# UVBoxSchematic_1_0.net
KiCad netlist of a schematic drawn in EAGLE
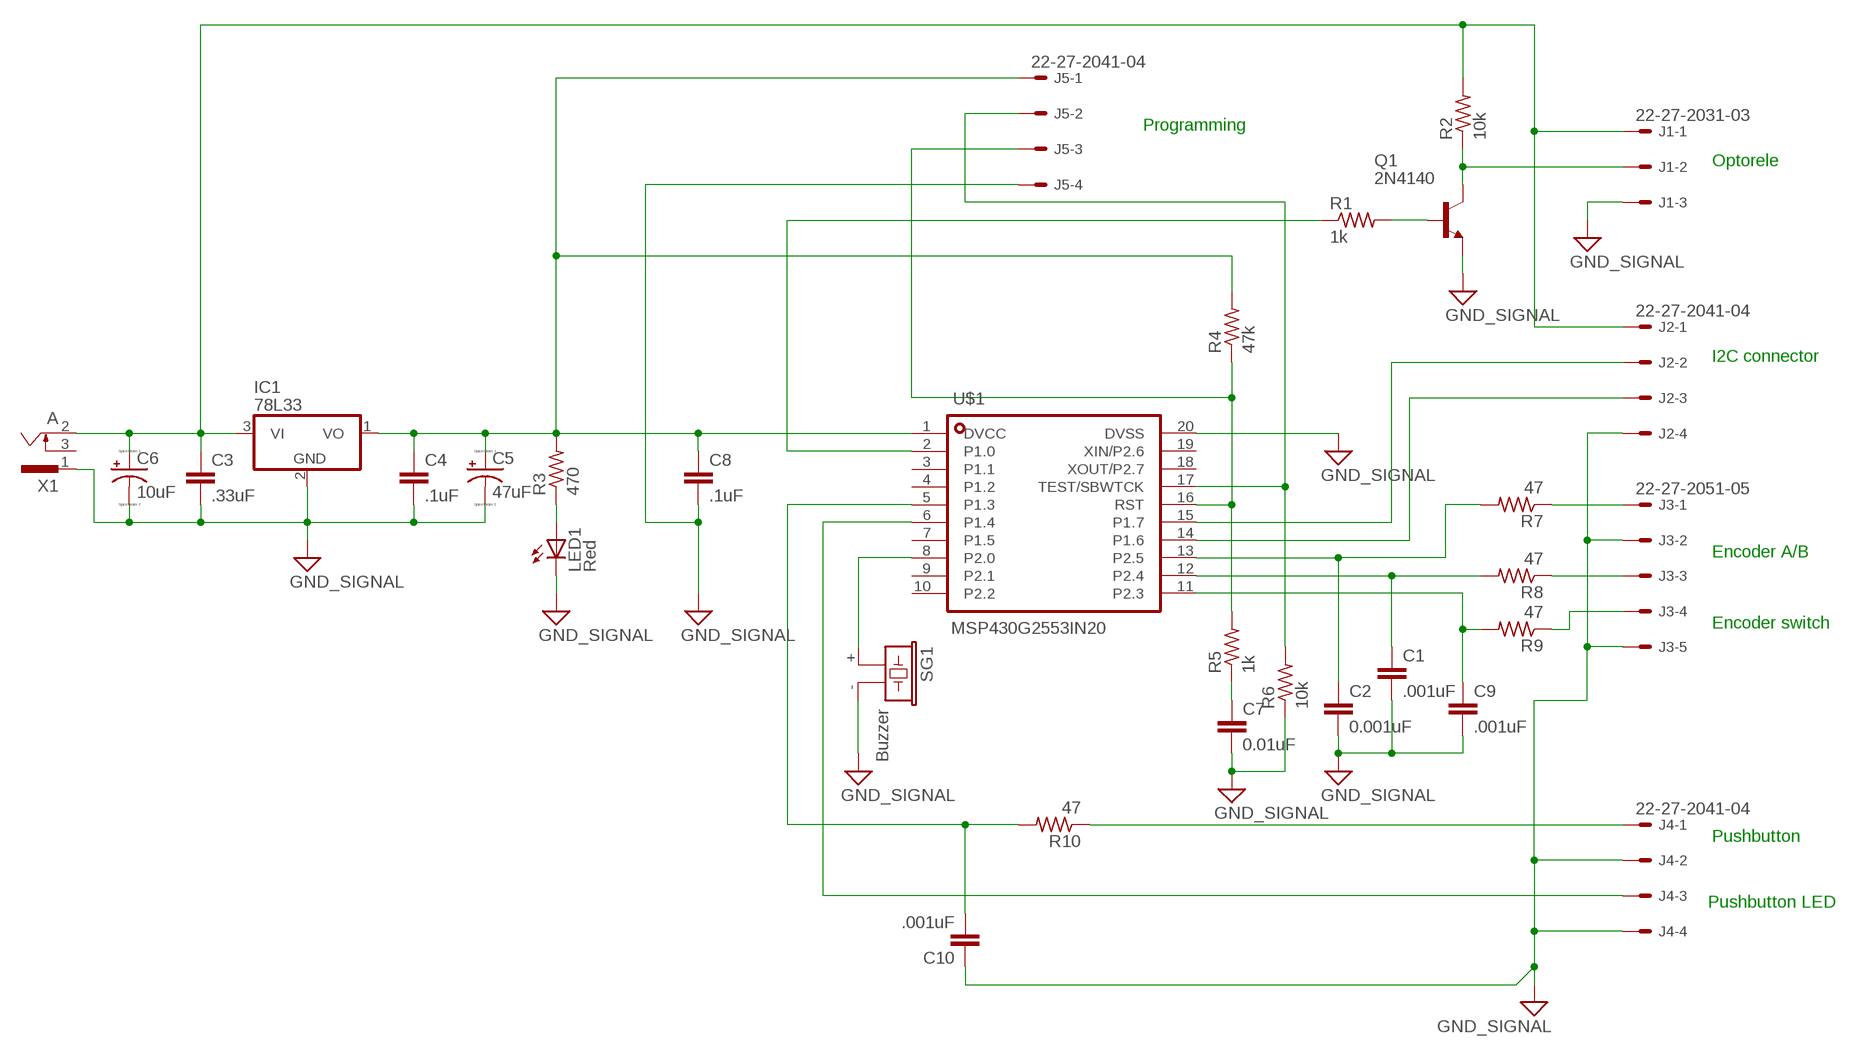
[diagram p0: schematic, sheet 1]

(export (version "E")
  (design (tool "Eeschema 10.0.6"))
  (components
    (comp (ref "C1")
      (value ".001uF")
      (footprint "eagle-import:C2.5-2")
      (libsource (lib "eagle-import") (part "C2.5/2"))
    )
    (comp (ref "C2")
      (value "0.001uF")
      (footprint "eagle-import:C2.5-2")
      (libsource (lib "eagle-import") (part "C2.5/2"))
    )
    (comp (ref "C3")
      (value ".33uF")
      (footprint "eagle-import:C2.5-2")
      (libsource (lib "eagle-import") (part "C2.5/2"))
    )
    (comp (ref "C4")
      (value ".1uF")
      (footprint "eagle-import:C2.5-2")
      (libsource (lib "eagle-import") (part "C2.5/2"))
    )
    (comp (ref "C5")
      (value "47uF")
      (footprint "eagle-import:B45181A")
      (libsource (lib "eagle-import") (part "CPOL-USB45181A"))
    )
    (comp (ref "C6")
      (value "10uF")
      (footprint "eagle-import:B45181A")
      (libsource (lib "eagle-import") (part "CPOL-USB45181A"))
    )
    (comp (ref "C7")
      (value "0.01uF")
      (footprint "eagle-import:C2.5-2")
      (libsource (lib "eagle-import") (part "C2.5/2"))
    )
    (comp (ref "C8")
      (value ".1uF")
      (footprint "eagle-import:C2.5-2")
      (libsource (lib "eagle-import") (part "C2.5/2"))
    )
    (comp (ref "C9")
      (value ".001uF")
      (footprint "eagle-import:C2.5-2")
      (libsource (lib "eagle-import") (part "C2.5/2"))
    )
    (comp (ref "C10")
      (value ".001uF")
      (footprint "eagle-import:C2.5-2")
      (libsource (lib "eagle-import") (part "C2.5/2"))
    )
    (comp (ref "IC1")
      (value "78L33")
      (footprint "eagle-import:TO92")
      (libsource (lib "eagle-import") (part "78ZL05"))
    )
    (comp (ref "J1")
      (value "22-27-2031-03")
      (footprint "eagle-import:6410-03")
      (libsource (lib "eagle-import") (part "22-?-0327-2031"))
    )
    (comp (ref "J2")
      (value "22-27-2041-04")
      (footprint "eagle-import:6410-04")
      (libsource (lib "eagle-import") (part "22-?-0427-2041"))
    )
    (comp (ref "J3")
      (value "22-27-2051-05")
      (footprint "eagle-import:6410-05")
      (libsource (lib "eagle-import") (part "22-?-0527-2051"))
    )
    (comp (ref "J4")
      (value "22-27-2041-04")
      (footprint "eagle-import:6410-04")
      (libsource (lib "eagle-import") (part "22-?-0427-2041"))
    )
    (comp (ref "J5")
      (value "22-27-2041-04")
      (footprint "eagle-import:6410-04")
      (libsource (lib "eagle-import") (part "22-?-0427-2041"))
    )
    (comp (ref "LED1")
      (value "Red")
      (footprint "eagle-import:LED3MM")
      (libsource (lib "eagle-import") (part "LED3MM"))
    )
    (comp (ref "Q1")
      (value "2N4140")
      (footprint "eagle-import:TO18")
      (libsource (lib "eagle-import") (part "2N4104"))
    )
    (comp (ref "R1")
      (value "1k")
      (footprint "eagle-import:0204_7")
      (libsource (lib "eagle-import") (part "R-US_0204/7"))
    )
    (comp (ref "R2")
      (value "10k")
      (footprint "eagle-import:0204_7")
      (libsource (lib "eagle-import") (part "R-US_0204/7"))
    )
    (comp (ref "R3")
      (value "470")
      (footprint "eagle-import:0204_7")
      (libsource (lib "eagle-import") (part "R-US_0204/7"))
    )
    (comp (ref "R4")
      (value "47k")
      (footprint "eagle-import:0204_7")
      (libsource (lib "eagle-import") (part "R-US_0204/7"))
    )
    (comp (ref "R5")
      (value "1k")
      (footprint "eagle-import:0204_7")
      (libsource (lib "eagle-import") (part "R-US_0204/7"))
    )
    (comp (ref "R6")
      (value "10k")
      (footprint "eagle-import:0204_7")
      (libsource (lib "eagle-import") (part "R-US_0204/7"))
    )
    (comp (ref "R7")
      (value "47")
      (footprint "eagle-import:0204_7")
      (libsource (lib "eagle-import") (part "R-US_0204/7"))
    )
    (comp (ref "R8")
      (value "47")
      (footprint "eagle-import:0204_7")
      (libsource (lib "eagle-import") (part "R-US_0204/7"))
    )
    (comp (ref "R9")
      (value "47")
      (footprint "eagle-import:0204_7")
      (libsource (lib "eagle-import") (part "R-US_0204/7"))
    )
    (comp (ref "R10")
      (value "47")
      (footprint "eagle-import:0204_7")
      (libsource (lib "eagle-import") (part "R-US_0204/7"))
    )
    (comp (ref "SG1")
      (value "Buzzer")
      (footprint "eagle-import:F_CM04P")
      (libsource (lib "eagle-import") (part "F/CM04P"))
    )
    (comp (ref "U$1")
      (value "MSP430G2553IN20")
      (footprint "eagle-import:DIP20")
      (libsource (lib "eagle-import") (part "MSP430G2553IN20"))
    )
    (comp (ref "X1")
      (value "A")
      (footprint "eagle-import:SCD-014-A")
      (libsource (lib "eagle-import") (part "SCD-014A"))
    )
  )
  (nets
    (net (code "1") (name "GND_SIGNAL") (class "Default")
      (node (ref "C1") (pin "2") (pinfunction "2_2") (pintype "passive"))
      (node (ref "C10") (pin "1") (pinfunction "1_1") (pintype "passive"))
      (node (ref "C2") (pin "2") (pinfunction "2_2") (pintype "passive"))
      (node (ref "C3") (pin "2") (pinfunction "2_2") (pintype "passive"))
      (node (ref "C4") (pin "2") (pinfunction "2_2") (pintype "passive"))
      (node (ref "C5") (pin "-") (pinfunction "-_-") (pintype "passive"))
      (node (ref "C6") (pin "-") (pinfunction "-_-") (pintype "passive"))
      (node (ref "C7") (pin "2") (pinfunction "2_2") (pintype "passive"))
      (node (ref "C8") (pin "2") (pinfunction "2_2") (pintype "passive"))
      (node (ref "C9") (pin "2") (pinfunction "2_2") (pintype "passive"))
      (node (ref "IC1") (pin "2") (pinfunction "GND_2") (pintype "passive"))
      (node (ref "J1") (pin "3") (pinfunction "S_3") (pintype "passive"))
      (node (ref "J2") (pin "4") (pinfunction "S_4") (pintype "passive"))
      (node (ref "J3") (pin "2") (pinfunction "S_2") (pintype "passive"))
      (node (ref "J3") (pin "5") (pinfunction "S_5") (pintype "passive"))
      (node (ref "J4") (pin "2") (pinfunction "S_2") (pintype "passive"))
      (node (ref "J4") (pin "4") (pinfunction "S_4") (pintype "passive"))
      (node (ref "J5") (pin "4") (pinfunction "S_4") (pintype "passive"))
      (node (ref "LED1") (pin "K") (pinfunction "C_K") (pintype "passive"))
      (node (ref "Q1") (pin "1") (pinfunction "E_1") (pintype "passive"))
      (node (ref "R6") (pin "1") (pinfunction "1_1") (pintype "passive"))
      (node (ref "SG1") (pin "-") (pinfunction "2_-") (pintype "passive"))
      (node (ref "U$1") (pin "20") (pinfunction "DVSS_20") (pintype "power_in"))
      (node (ref "X1") (pin "1") (pinfunction "1_1") (pintype "passive"))
    )
    (net (code "2") (name "Net-(C7-Pad1)") (class "Default")
      (node (ref "C7") (pin "1") (pinfunction "1_1") (pintype "passive"))
      (node (ref "R5") (pin "1") (pinfunction "1_1") (pintype "passive"))
    )
    (net (code "3") (name "Net-(IC1-VI)") (class "Default")
      (node (ref "C3") (pin "1") (pinfunction "1_1") (pintype "passive"))
      (node (ref "C6") (pin "+") (pinfunction "+_+") (pintype "passive"))
      (node (ref "IC1") (pin "3") (pinfunction "VI_3") (pintype "input"))
      (node (ref "J1") (pin "1") (pinfunction "S_1") (pintype "passive"))
      (node (ref "J2") (pin "1") (pinfunction "S_1") (pintype "passive"))
      (node (ref "R2") (pin "2") (pinfunction "2_2") (pintype "passive"))
      (node (ref "X1") (pin "2") (pinfunction "2_2") (pintype "passive"))
    )
    (net (code "4") (name "Net-(IC1-VO)") (class "Default")
      (node (ref "C4") (pin "1") (pinfunction "1_1") (pintype "passive"))
      (node (ref "C5") (pin "+") (pinfunction "+_+") (pintype "passive"))
      (node (ref "C8") (pin "1") (pinfunction "1_1") (pintype "passive"))
      (node (ref "IC1") (pin "1") (pinfunction "VO_1") (pintype "passive"))
      (node (ref "J5") (pin "1") (pinfunction "S_1") (pintype "passive"))
      (node (ref "R3") (pin "2") (pinfunction "2_2") (pintype "passive"))
      (node (ref "R4") (pin "2") (pinfunction "2_2") (pintype "passive"))
      (node (ref "U$1") (pin "1") (pinfunction "DVCC_1") (pintype "power_in"))
    )
    (net (code "5") (name "Net-(J1B-S)") (class "Default")
      (node (ref "J1") (pin "2") (pinfunction "S_2") (pintype "passive"))
      (node (ref "Q1") (pin "3") (pinfunction "C_3") (pintype "passive"))
      (node (ref "R2") (pin "1") (pinfunction "1_1") (pintype "passive"))
    )
    (net (code "6") (name "Net-(J2B-S)") (class "Default")
      (node (ref "J2") (pin "2") (pinfunction "S_2") (pintype "passive"))
      (node (ref "U$1") (pin "15") (pinfunction "P1.7_15") (pintype "bidirectional"))
    )
    (net (code "7") (name "Net-(J2C-S)") (class "Default")
      (node (ref "J2") (pin "3") (pinfunction "S_3") (pintype "passive"))
      (node (ref "U$1") (pin "14") (pinfunction "P1.6_14") (pintype "bidirectional"))
    )
    (net (code "8") (name "Net-(J3A-S)") (class "Default")
      (node (ref "J3") (pin "1") (pinfunction "S_1") (pintype "passive"))
      (node (ref "R7") (pin "1") (pinfunction "1_1") (pintype "passive"))
    )
    (net (code "9") (name "Net-(J3C-S)") (class "Default")
      (node (ref "J3") (pin "3") (pinfunction "S_3") (pintype "passive"))
      (node (ref "R8") (pin "1") (pinfunction "1_1") (pintype "passive"))
    )
    (net (code "10") (name "Net-(J3D-S)") (class "Default")
      (node (ref "J3") (pin "4") (pinfunction "S_4") (pintype "passive"))
      (node (ref "R9") (pin "1") (pinfunction "1_1") (pintype "passive"))
    )
    (net (code "11") (name "Net-(J4A-S)") (class "Default")
      (node (ref "J4") (pin "1") (pinfunction "S_1") (pintype "passive"))
      (node (ref "R10") (pin "1") (pinfunction "1_1") (pintype "passive"))
    )
    (net (code "12") (name "Net-(J4C-S)") (class "Default")
      (node (ref "J4") (pin "3") (pinfunction "S_3") (pintype "passive"))
      (node (ref "U$1") (pin "6") (pinfunction "P1.4_6") (pintype "bidirectional"))
    )
    (net (code "13") (name "Net-(J5B-S)") (class "Default")
      (node (ref "J5") (pin "2") (pinfunction "S_2") (pintype "passive"))
      (node (ref "R6") (pin "2") (pinfunction "2_2") (pintype "passive"))
      (node (ref "U$1") (pin "17") (pinfunction "TEST/SBWTCK_17") (pintype "bidirectional"))
    )
    (net (code "14") (name "Net-(J5C-S)") (class "Default")
      (node (ref "J5") (pin "3") (pinfunction "S_3") (pintype "passive"))
      (node (ref "R4") (pin "1") (pinfunction "1_1") (pintype "passive"))
      (node (ref "R5") (pin "2") (pinfunction "2_2") (pintype "passive"))
      (node (ref "U$1") (pin "16") (pinfunction "RST_16") (pintype "bidirectional"))
    )
    (net (code "15") (name "Net-(LED1-PadA)") (class "Default")
      (node (ref "LED1") (pin "A") (pinfunction "A_A") (pintype "passive"))
      (node (ref "R3") (pin "1") (pinfunction "1_1") (pintype "passive"))
    )
    (net (code "16") (name "Net-(Q1-B)") (class "Default")
      (node (ref "Q1") (pin "2") (pinfunction "B_2") (pintype "passive"))
      (node (ref "R1") (pin "2") (pinfunction "2_2") (pintype "passive"))
    )
    (net (code "17") (name "Net-(SG1-1)") (class "Default")
      (node (ref "SG1") (pin "+") (pinfunction "1_+") (pintype "passive"))
      (node (ref "U$1") (pin "8") (pinfunction "P2.0_8") (pintype "bidirectional"))
    )
    (net (code "18") (name "Net-(U$1-P1.0)") (class "Default")
      (node (ref "R1") (pin "1") (pinfunction "1_1") (pintype "passive"))
      (node (ref "U$1") (pin "2") (pinfunction "P1.0_2") (pintype "bidirectional"))
    )
    (net (code "19") (name "Net-(U$1-P1.3)") (class "Default")
      (node (ref "C10") (pin "2") (pinfunction "2_2") (pintype "passive"))
      (node (ref "R10") (pin "2") (pinfunction "2_2") (pintype "passive"))
      (node (ref "U$1") (pin "5") (pinfunction "P1.3_5") (pintype "bidirectional"))
    )
    (net (code "20") (name "Net-(U$1-P2.3)") (class "Default")
      (node (ref "C9") (pin "1") (pinfunction "1_1") (pintype "passive"))
      (node (ref "R9") (pin "2") (pinfunction "2_2") (pintype "passive"))
      (node (ref "U$1") (pin "11") (pinfunction "P2.3_11") (pintype "bidirectional"))
    )
    (net (code "21") (name "Net-(U$1-P2.4)") (class "Default")
      (node (ref "C1") (pin "1") (pinfunction "1_1") (pintype "passive"))
      (node (ref "R8") (pin "2") (pinfunction "2_2") (pintype "passive"))
      (node (ref "U$1") (pin "12") (pinfunction "P2.4_12") (pintype "bidirectional"))
    )
    (net (code "22") (name "Net-(U$1-P2.5)") (class "Default")
      (node (ref "C2") (pin "1") (pinfunction "1_1") (pintype "passive"))
      (node (ref "R7") (pin "2") (pinfunction "2_2") (pintype "passive"))
      (node (ref "U$1") (pin "13") (pinfunction "P2.5_13") (pintype "bidirectional"))
    )
    (net (code "23") (name "unconnected-(U$1-P1.1-Pad3)") (class "Default")
      (node (ref "U$1") (pin "3") (pinfunction "P1.1_3") (pintype "bidirectional"))
    )
    (net (code "24") (name "unconnected-(U$1-P1.2-Pad4)") (class "Default")
      (node (ref "U$1") (pin "4") (pinfunction "P1.2_4") (pintype "bidirectional"))
    )
    (net (code "25") (name "unconnected-(U$1-P1.5-Pad7)") (class "Default")
      (node (ref "U$1") (pin "7") (pinfunction "P1.5_7") (pintype "bidirectional"))
    )
    (net (code "26") (name "unconnected-(U$1-P2.1-Pad9)") (class "Default")
      (node (ref "U$1") (pin "9") (pinfunction "P2.1_9") (pintype "bidirectional"))
    )
    (net (code "27") (name "unconnected-(U$1-P2.2-Pad10)") (class "Default")
      (node (ref "U$1") (pin "10") (pinfunction "P2.2_10") (pintype "bidirectional"))
    )
    (net (code "28") (name "unconnected-(U$1-XIN{slash}P2.6-Pad19)") (class "Default")
      (node (ref "U$1") (pin "19") (pinfunction "XIN/P2.6_19") (pintype "bidirectional"))
    )
    (net (code "29") (name "unconnected-(U$1-XOUT{slash}P2.7-Pad18)") (class "Default")
      (node (ref "U$1") (pin "18") (pinfunction "XOUT/P2.7_18") (pintype "bidirectional"))
    )
    (net (code "30") (name "unconnected-(X1-Pad3)") (class "Default")
      (node (ref "X1") (pin "3") (pinfunction "3_3") (pintype "passive"))
    )
  )
)
